# wifiswitch.net
KiCad netlist of a schematic drawn in EAGLE
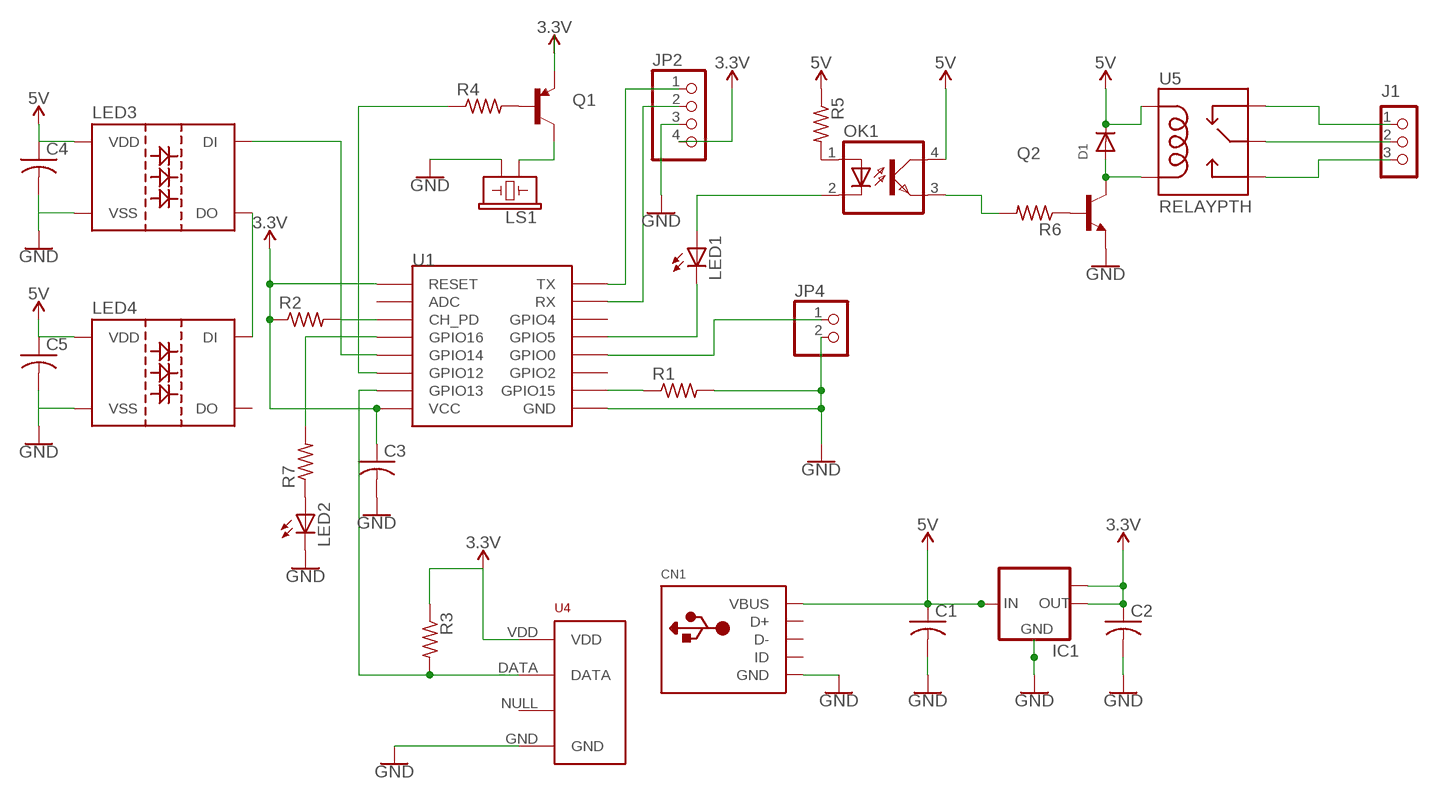
[diagram p0: schematic, sheet 1]

(export (version "E")
  (design (tool "Eeschema 10.0.6"))
  (components
    (comp (ref "C1")
      (value "C-USC0805")
      (footprint "eagle-import:C0805")
      (libsource (lib "eagle-import") (part "C-USC0805"))
    )
    (comp (ref "C2")
      (value "C-USC0805")
      (footprint "eagle-import:C0805")
      (libsource (lib "eagle-import") (part "C-USC0805"))
    )
    (comp (ref "C3")
      (value "C-USC0805")
      (footprint "eagle-import:C0805")
      (fields (field (name "MPN") "C0805X104J5RAC3316"))
      (libsource (lib "eagle-import") (part "C-USC0805"))
    )
    (comp (ref "C4")
      (value "C-USC0805")
      (footprint "eagle-import:C0805")
      (fields (field (name "MPN") "C0805X104J5RAC3316"))
      (libsource (lib "eagle-import") (part "C-USC0805"))
    )
    (comp (ref "C5")
      (value "C-USC0805")
      (footprint "eagle-import:C0805")
      (fields (field (name "MPN") "C0805X104J5RAC3316"))
      (libsource (lib "eagle-import") (part "C-USC0805"))
    )
    (comp (ref "CN1")
      (value "USBTHM")
      (footprint "eagle-import:USB-MINIB-THM")
      (libsource (lib "eagle-import") (part "USBTHM"))
    )
    (comp (ref "D1")
      (value "DIODESOD-123")
      (footprint "eagle-import:SOD-123")
      (libsource (lib "eagle-import") (part "DIODESOD-123"))
    )
    (comp (ref "IC1")
      (value "LM1117IMPX-3.3")
      (footprint "eagle-import:SOT223")
      (fields (field (name "MPN") "ADP3339AKCZ-3.3-R7"))
      (libsource (lib "eagle-import") (part "LM1117IMPX-3.3"))
    )
    (comp (ref "J1")
      (value "CON_TERMINAL_BLOCK_03-5MM")
      (footprint "eagle-import:TERMINAL_BLOCK_3P_5")
      (libsource (lib "eagle-import") (part "CON_TERMINAL_BLOCK_03-5MM"))
    )
    (comp (ref "JP2")
      (value "PINHD-1X4")
      (footprint "eagle-import:1X04")
      (libsource (lib "eagle-import") (part "PINHD-1X4"))
    )
    (comp (ref "JP4")
      (value "PINHD-1X2")
      (footprint "eagle-import:1X02")
      (libsource (lib "eagle-import") (part "PINHD-1X2"))
    )
    (comp (ref "LED1")
      (value "LEDCHIP-LED0805")
      (footprint "eagle-import:CHIP-LED0805")
      (libsource (lib "eagle-import") (part "LEDCHIP-LED0805"))
    )
    (comp (ref "LED2")
      (value "LEDCHIP-LED0805")
      (footprint "eagle-import:CHIP-LED0805")
      (libsource (lib "eagle-import") (part "LEDCHIP-LED0805"))
    )
    (comp (ref "LED3")
      (value "WS2812B")
      (footprint "eagle-import:WS2812B")
      (libsource (lib "eagle-import") (part "WS2812B"))
    )
    (comp (ref "LED4")
      (value "WS2812B")
      (footprint "eagle-import:WS2812B")
      (libsource (lib "eagle-import") (part "WS2812B"))
    )
    (comp (ref "LS1")
      (value "BUZZER-PTH")
      (footprint "eagle-import:BUZZER-12MM")
      (libsource (lib "eagle-import") (part "BUZZER-PTH"))
    )
    (comp (ref "OK1")
      (value "PC817")
      (footprint "eagle-import:DIL04")
      (fields (field (name "MPN") "PC817X4J000F"))
      (libsource (lib "eagle-import") (part "PC817"))
    )
    (comp (ref "Q1")
      (value "TRANSISTOR_PNPPMBT3906")
      (footprint "eagle-import:SOT23-3")
      (libsource (lib "eagle-import") (part "TRANSISTOR_PNPPMBT3906"))
    )
    (comp (ref "Q2")
      (value "TRANSISTOR_BJT_NPN-SOT-23-BEC")
      (footprint "eagle-import:SOT-23")
      (libsource (lib "eagle-import") (part "TRANSISTOR_BJT_NPN-SOT-23-BEC"))
    )
    (comp (ref "R1")
      (value "R-US_R0805")
      (footprint "eagle-import:R0805")
      (libsource (lib "eagle-import") (part "R-US_R0805"))
    )
    (comp (ref "R2")
      (value "R-US_R0805")
      (footprint "eagle-import:R0805")
      (libsource (lib "eagle-import") (part "R-US_R0805"))
    )
    (comp (ref "R3")
      (value "R-US_R0805")
      (footprint "eagle-import:R0805")
      (libsource (lib "eagle-import") (part "R-US_R0805"))
    )
    (comp (ref "R4")
      (value "R-US_R0805")
      (footprint "eagle-import:R0805")
      (libsource (lib "eagle-import") (part "R-US_R0805"))
    )
    (comp (ref "R5")
      (value "R-US_R0805")
      (footprint "eagle-import:R0805")
      (libsource (lib "eagle-import") (part "R-US_R0805"))
    )
    (comp (ref "R6")
      (value "R-US_R0805")
      (footprint "eagle-import:R0805")
      (libsource (lib "eagle-import") (part "R-US_R0805"))
    )
    (comp (ref "R7")
      (value "R-US_R0805")
      (footprint "eagle-import:R0805")
      (libsource (lib "eagle-import") (part "R-US_R0805"))
    )
    (comp (ref "U1")
      (value "ESP12SMD")
      (footprint "eagle-import:ESP12-SMD")
      (libsource (lib "eagle-import") (part "ESP12SMD"))
    )
    (comp (ref "U4")
      (value "RHT03_DHT-22_AM2302RA")
      (footprint "eagle-import:RHT03_DHT-22_RA")
      (libsource (lib "eagle-import") (part "RHT03_DHT-22_AM2302RA"))
    )
    (comp (ref "U5")
      (value "RELAYPTH")
      (footprint "eagle-import:SRD-05VDC-SL-C")
      (libsource (lib "eagle-import") (part "RELAYPTH"))
    )
  )
  (nets
    (net (code "1") (name "3.3V") (class "Default")
      (node (ref "C2") (pin "1") (pinfunction "1_1") (pintype "passive"))
      (node (ref "C3") (pin "1") (pinfunction "1_1") (pintype "passive"))
      (node (ref "IC1") (pin "2") (pinfunction "OUT_2") (pintype "passive"))
      (node (ref "IC1") (pin "TAB") (pinfunction "OUT1_TAB") (pintype "passive"))
      (node (ref "JP2") (pin "4") (pinfunction "4_4") (pintype "passive"))
      (node (ref "Q1") (pin "2") (pinfunction "E_2") (pintype "passive"))
      (node (ref "R2") (pin "1") (pinfunction "1_1") (pintype "passive"))
      (node (ref "R3") (pin "1") (pinfunction "1_1") (pintype "passive"))
      (node (ref "U1") (pin "RESET") (pinfunction "RESET_RESET") (pintype "bidirectional"))
      (node (ref "U1") (pin "VCC") (pinfunction "VCC_VCC") (pintype "bidirectional"))
      (node (ref "U4") (pin "VDD") (pinfunction "VDD_VDD") (pintype "power_in"))
    )
    (net (code "2") (name "5V") (class "Default")
      (node (ref "C1") (pin "1") (pinfunction "1_1") (pintype "passive"))
      (node (ref "C4") (pin "1") (pinfunction "1_1") (pintype "passive"))
      (node (ref "C5") (pin "1") (pinfunction "1_1") (pintype "passive"))
      (node (ref "CN1") (pin "VBUS") (pinfunction "VBUS_VBUS") (pintype "power_in"))
      (node (ref "D1") (pin "C") (pinfunction "C_C") (pintype "passive"))
      (node (ref "IC1") (pin "3") (pinfunction "IN_3") (pintype "input"))
      (node (ref "LED3") (pin "1") (pinfunction "VDD_1") (pintype "bidirectional"))
      (node (ref "LED4") (pin "1") (pinfunction "VDD_1") (pintype "bidirectional"))
      (node (ref "OK1") (pin "4") (pinfunction "COL_4") (pintype "passive"))
      (node (ref "R5") (pin "1") (pinfunction "1_1") (pintype "passive"))
      (node (ref "U5") (pin "P$1") (pinfunction "COIL1_P$1") (pintype "bidirectional"))
    )
    (net (code "3") (name "GND") (class "Default")
      (node (ref "C1") (pin "2") (pinfunction "2_2") (pintype "passive"))
      (node (ref "C2") (pin "2") (pinfunction "2_2") (pintype "passive"))
      (node (ref "C3") (pin "2") (pinfunction "2_2") (pintype "passive"))
      (node (ref "C4") (pin "2") (pinfunction "2_2") (pintype "passive"))
      (node (ref "C5") (pin "2") (pinfunction "2_2") (pintype "passive"))
      (node (ref "CN1") (pin "GND") (pinfunction "GND_GND") (pintype "power_in"))
      (node (ref "IC1") (pin "1") (pinfunction "GND_1") (pintype "input"))
      (node (ref "JP2") (pin "3") (pinfunction "3_3") (pintype "passive"))
      (node (ref "JP4") (pin "2") (pinfunction "2_2") (pintype "passive"))
      (node (ref "LED2") (pin "C") (pinfunction "C_C") (pintype "passive"))
      (node (ref "LED3") (pin "3") (pinfunction "VSS_3") (pintype "bidirectional"))
      (node (ref "LED4") (pin "3") (pinfunction "VSS_3") (pintype "bidirectional"))
      (node (ref "LS1") (pin "-") (pinfunction "2_-") (pintype "passive"))
      (node (ref "Q2") (pin "2") (pinfunction "E_2") (pintype "passive"))
      (node (ref "R1") (pin "2") (pinfunction "2_2") (pintype "passive"))
      (node (ref "U1") (pin "GND") (pinfunction "GND_GND") (pintype "bidirectional"))
      (node (ref "U4") (pin "GND") (pinfunction "GND_GND") (pintype "power_in"))
    )
    (net (code "4") (name "Net-(JP4-Pad1)") (class "Default")
      (node (ref "JP4") (pin "1") (pinfunction "1_1") (pintype "passive"))
      (node (ref "U1") (pin "GPIO0") (pinfunction "GPIO0_GPIO0") (pintype "bidirectional"))
    )
    (net (code "5") (name "Net-(LED1-PadC)") (class "Default")
      (node (ref "LED1") (pin "C") (pinfunction "C_C") (pintype "passive"))
      (node (ref "U1") (pin "GPIO5") (pinfunction "GPIO5_GPIO5") (pintype "bidirectional"))
    )
    (net (code "6") (name "Net-(LED2-PadA)") (class "Default")
      (node (ref "LED2") (pin "A") (pinfunction "A_A") (pintype "passive"))
      (node (ref "R7") (pin "1") (pinfunction "1_1") (pintype "passive"))
    )
    (net (code "7") (name "Net-(LED3-DI)") (class "Default")
      (node (ref "LED3") (pin "4") (pinfunction "DI_4") (pintype "bidirectional"))
      (node (ref "U1") (pin "GPIO14") (pinfunction "GPIO14_GPIO14") (pintype "bidirectional"))
    )
    (net (code "8") (name "Net-(LED3-DO)") (class "Default")
      (node (ref "LED3") (pin "2") (pinfunction "DO_2") (pintype "bidirectional"))
      (node (ref "LED4") (pin "4") (pinfunction "DI_4") (pintype "bidirectional"))
    )
    (net (code "9") (name "Net-(LS1-1)") (class "Default")
      (node (ref "LS1") (pin "+") (pinfunction "1_+") (pintype "passive"))
      (node (ref "Q1") (pin "3") (pinfunction "C_3") (pintype "passive"))
    )
    (net (code "10") (name "Net-(OK1-A)") (class "Default")
      (node (ref "OK1") (pin "1") (pinfunction "A_1") (pintype "passive"))
      (node (ref "R5") (pin "2") (pinfunction "2_2") (pintype "passive"))
    )
    (net (code "11") (name "Net-(OK1-C)") (class "Default")
      (node (ref "LED1") (pin "A") (pinfunction "A_A") (pintype "passive"))
      (node (ref "OK1") (pin "2") (pinfunction "C_2") (pintype "passive"))
    )
    (net (code "12") (name "Net-(OK1-EMIT)") (class "Default")
      (node (ref "OK1") (pin "3") (pinfunction "EMIT_3") (pintype "passive"))
      (node (ref "R6") (pin "2") (pinfunction "2_2") (pintype "passive"))
    )
    (net (code "13") (name "Net-(Q1-B)") (class "Default")
      (node (ref "Q1") (pin "1") (pinfunction "B_1") (pintype "passive"))
      (node (ref "R4") (pin "2") (pinfunction "2_2") (pintype "passive"))
    )
    (net (code "14") (name "Net-(Q2-B)") (class "Default")
      (node (ref "Q2") (pin "1") (pinfunction "B_1") (pintype "passive"))
      (node (ref "R6") (pin "1") (pinfunction "1_1") (pintype "passive"))
    )
    (net (code "15") (name "Net-(Q2-C)") (class "Default")
      (node (ref "D1") (pin "A") (pinfunction "A_A") (pintype "passive"))
      (node (ref "Q2") (pin "3") (pinfunction "C_3") (pintype "passive"))
      (node (ref "U5") (pin "P$4") (pinfunction "COIL0_P$4") (pintype "bidirectional"))
    )
    (net (code "16") (name "Net-(R1-Pad1)") (class "Default")
      (node (ref "R1") (pin "1") (pinfunction "1_1") (pintype "passive"))
      (node (ref "U1") (pin "GPIO15") (pinfunction "GPIO15_GPIO15") (pintype "bidirectional"))
    )
    (net (code "17") (name "Net-(R2-Pad2)") (class "Default")
      (node (ref "R2") (pin "2") (pinfunction "2_2") (pintype "passive"))
      (node (ref "U1") (pin "CH_PD") (pinfunction "CH_PD_CH_PD") (pintype "bidirectional"))
    )
    (net (code "18") (name "Net-(R3-Pad2)") (class "Default")
      (node (ref "R3") (pin "2") (pinfunction "2_2") (pintype "passive"))
      (node (ref "U1") (pin "GPIO13") (pinfunction "GPIO13_GPIO13") (pintype "bidirectional"))
      (node (ref "U4") (pin "DATA") (pinfunction "DATA_DATA") (pintype "bidirectional"))
    )
    (net (code "19") (name "Net-(R4-Pad1)") (class "Default")
      (node (ref "R4") (pin "1") (pinfunction "1_1") (pintype "passive"))
      (node (ref "U1") (pin "GPIO12") (pinfunction "GPIO12_GPIO12") (pintype "bidirectional"))
    )
    (net (code "20") (name "Net-(R7-Pad2)") (class "Default")
      (node (ref "R7") (pin "2") (pinfunction "2_2") (pintype "passive"))
      (node (ref "U1") (pin "GPIO16") (pinfunction "GPIO16_GPIO16") (pintype "bidirectional"))
    )
    (net (code "21") (name "Net-(U1-RX)") (class "Default")
      (node (ref "JP2") (pin "2") (pinfunction "2_2") (pintype "passive"))
      (node (ref "U1") (pin "RXD0") (pinfunction "RX_RXD0") (pintype "bidirectional"))
    )
    (net (code "22") (name "Net-(U1-TX)") (class "Default")
      (node (ref "JP2") (pin "1") (pinfunction "1_1") (pintype "passive"))
      (node (ref "U1") (pin "TXD0") (pinfunction "TX_TXD0") (pintype "bidirectional"))
    )
    (net (code "23") (name "Net-(U5-SWCLOSE)") (class "Default")
      (node (ref "J1") (pin "1") (pinfunction "1_1") (pintype "bidirectional"))
      (node (ref "U5") (pin "P$5") (pinfunction "SWCLOSE_P$5") (pintype "bidirectional"))
    )
    (net (code "24") (name "Net-(U5-SWCOMMON)") (class "Default")
      (node (ref "J1") (pin "2") (pinfunction "2_2") (pintype "bidirectional"))
      (node (ref "U5") (pin "P$3") (pinfunction "SWCOMMON_P$3") (pintype "bidirectional"))
    )
    (net (code "25") (name "Net-(U5-SWOPEN)") (class "Default")
      (node (ref "J1") (pin "3") (pinfunction "3_3") (pintype "bidirectional"))
      (node (ref "U5") (pin "P$2") (pinfunction "SWOPEN_P$2") (pintype "bidirectional"))
    )
    (net (code "26") (name "unconnected-(CN1-PadD+)") (class "Default")
      (node (ref "CN1") (pin "D+") (pinfunction "D+_D+") (pintype "bidirectional"))
    )
    (net (code "27") (name "unconnected-(CN1-PadD-)") (class "Default")
      (node (ref "CN1") (pin "D-") (pinfunction "D-_D-") (pintype "bidirectional"))
    )
    (net (code "28") (name "unconnected-(CN1-PadID)") (class "Default")
      (node (ref "CN1") (pin "ID") (pinfunction "ID_ID") (pintype "bidirectional"))
    )
    (net (code "29") (name "unconnected-(LED4-DO-Pad2)") (class "Default")
      (node (ref "LED4") (pin "2") (pinfunction "DO_2") (pintype "bidirectional"))
    )
    (net (code "30") (name "unconnected-(U1-PadADC)") (class "Default")
      (node (ref "U1") (pin "ADC") (pinfunction "ADC_ADC") (pintype "bidirectional"))
    )
    (net (code "31") (name "unconnected-(U1-PadGPIO2)") (class "Default")
      (node (ref "U1") (pin "GPIO2") (pinfunction "GPIO2_GPIO2") (pintype "bidirectional"))
    )
    (net (code "32") (name "unconnected-(U1-PadGPIO4)") (class "Default")
      (node (ref "U1") (pin "GPIO4") (pinfunction "GPIO4_GPIO4") (pintype "bidirectional"))
    )
    (net (code "33") (name "unconnected-(U4-PadNULL)") (class "Default")
      (node (ref "U4") (pin "NULL") (pinfunction "NULL_NULL") (pintype "no_connect"))
    )
  )
)
